# Main.net
KiCad netlist of a schematic drawn in Altium Designer
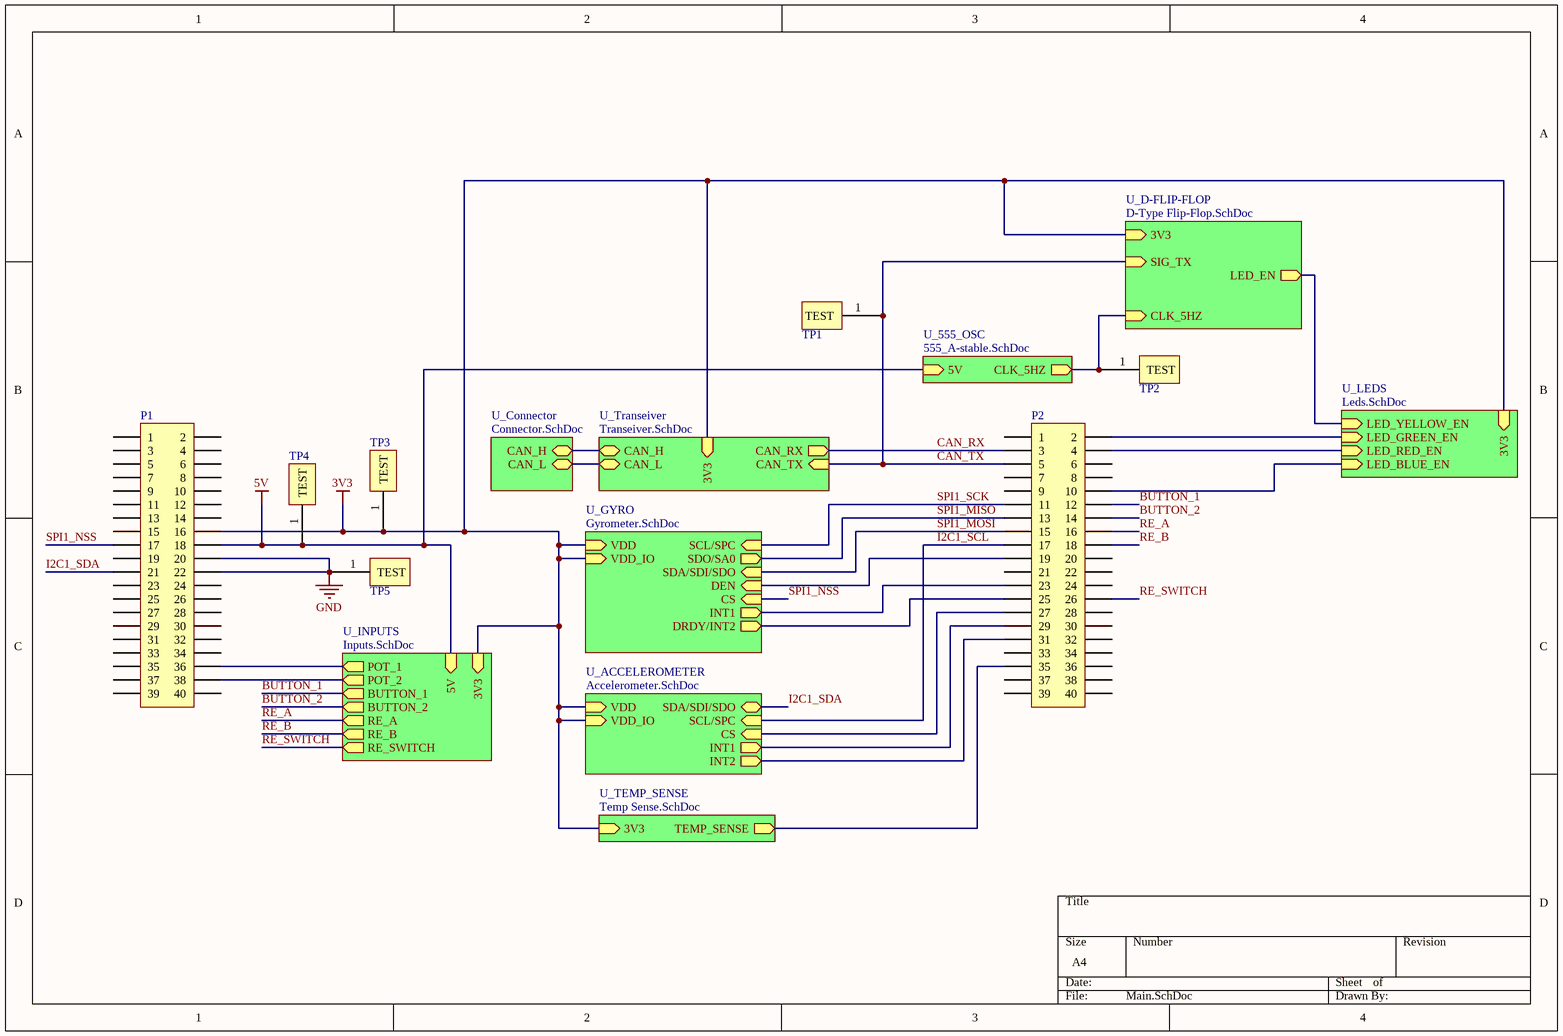
[diagram p0: Main.SchDoc]

(export (version "E")
  (design (tool "Eeschema 10.0.6"))
  (components
    (comp (ref "P1")
      (value "Female Header 20x2_BOTTOM")
      (footprint "FEMALE HDR2X20_BOTTOM")
      (description "CONN HEADR FMALE 20POS .1\" DL AU")
      (libsource (lib "Connectors and Headers") (part "Female Header 20x2_BOTTOM"))
    )
    (comp (ref "P2")
      (value "Female Header 20x2_BOTTOM")
      (footprint "FEMALE HDR2X20_BOTTOM")
      (description "CONN HEADR FMALE 20POS .1\" DL AU")
      (libsource (lib "Connectors and Headers") (part "Female Header 20x2_BOTTOM"))
    )
    (comp (ref "TP1")
      (value "Keystone Electronics 5000")
      (footprint "TEST POINT 5000K")
      (description "TEST POINT PC MINI .040\"D RED")
      (libsource (lib "") (part "Keystone Electronics 5000_2"))
    )
    (comp (ref "TP2")
      (value "Keystone Electronics 5000")
      (footprint "TEST POINT 5000K")
      (description "TEST POINT PC MINI .040\"D RED")
      (libsource (lib "") (part "Keystone Electronics 5000_1"))
    )
    (comp (ref "TP3")
      (value "Keystone Electronics 5000")
      (footprint "TEST POINT 5000K")
      (description "TEST POINT PC MINI .040\"D RED")
      (libsource (lib "Mechanical_Devices") (part "Keystone Electronics 5000"))
    )
    (comp (ref "TP4")
      (value "Keystone Electronics 5000")
      (footprint "TEST POINT 5000K")
      (description "TEST POINT PC MINI .040\"D RED")
      (libsource (lib "Mechanical_Devices") (part "Keystone Electronics 5000"))
    )
    (comp (ref "TP5")
      (value "Keystone Electronics 5000")
      (footprint "TEST POINT 5000K")
      (description "TEST POINT PC MINI .040\"D RED")
      (libsource (lib "") (part "Keystone Electronics 5000_1"))
    )
  )
  (nets
    (net (code "1") (name "/BUTTON_1") (class "Default")
      (node (ref "P2") (pin "12") (pinfunction "12_12") (pintype "passive"))
    )
    (net (code "2") (name "/BUTTON_2") (class "Default")
      (node (ref "P2") (pin "14") (pinfunction "14_14") (pintype "passive"))
    )
    (net (code "5") (name "/CAN_RX") (class "Default")
      (node (ref "P2") (pin "3") (pinfunction "3_3") (pintype "passive"))
    )
    (net (code "6") (name "/CAN_TX") (class "Default")
      (node (ref "P2") (pin "5") (pinfunction "5_5") (pintype "passive"))
      (node (ref "TP1") (pin "1") (pinfunction "TEST_1") (pintype "passive"))
    )
    (net (code "7") (name "/CLK_5HZ") (class "Default")
      (node (ref "TP2") (pin "1") (pinfunction "TEST_1") (pintype "passive"))
    )
    (net (code "8") (name "/CS") (class "Default")
      (node (ref "P2") (pin "27") (pinfunction "27_27") (pintype "passive"))
    )
    (net (code "9") (name "/DEN") (class "Default")
      (node (ref "P2") (pin "19") (pinfunction "19_19") (pintype "passive"))
    )
    (net (code "10") (name "/DRDY{slash}INT2") (class "Default")
      (node (ref "P2") (pin "25") (pinfunction "25_25") (pintype "passive"))
    )
    (net (code "11") (name "/I2C1_SCL") (class "Default")
      (node (ref "P2") (pin "17") (pinfunction "17_17") (pintype "passive"))
    )
    (net (code "12") (name "/I2C1_SDA") (class "Default")
      (node (ref "P1") (pin "21") (pinfunction "21_21") (pintype "passive"))
    )
    (net (code "13") (name "/INT1") (class "Default")
      (node (ref "P2") (pin "29") (pinfunction "29_29") (pintype "passive"))
    )
    (net (code "14") (name "/INT1_1") (class "Default")
      (node (ref "P2") (pin "23") (pinfunction "23_23") (pintype "passive"))
    )
    (net (code "15") (name "/INT2") (class "Default")
      (node (ref "P2") (pin "31") (pinfunction "31_31") (pintype "passive"))
    )
    (net (code "16") (name "/LED_BLUE_EN") (class "Default")
      (node (ref "P2") (pin "10") (pinfunction "10_10") (pintype "passive"))
    )
    (net (code "18") (name "/LED_GREEN_EN") (class "Default")
      (node (ref "P2") (pin "2") (pinfunction "2_2") (pintype "passive"))
    )
    (net (code "19") (name "/LED_RED_EN") (class "Default")
      (node (ref "P2") (pin "4") (pinfunction "4_4") (pintype "passive"))
    )
    (net (code "20") (name "/POT_1") (class "Default")
      (node (ref "P1") (pin "36") (pinfunction "36_36") (pintype "passive"))
    )
    (net (code "21") (name "/POT_2") (class "Default")
      (node (ref "P1") (pin "38") (pinfunction "38_38") (pintype "passive"))
    )
    (net (code "22") (name "/RE_A") (class "Default")
      (node (ref "P2") (pin "16") (pinfunction "16_16") (pintype "passive"))
    )
    (net (code "23") (name "/RE_B") (class "Default")
      (node (ref "P2") (pin "18") (pinfunction "18_18") (pintype "passive"))
    )
    (net (code "24") (name "/RE_SWITCH") (class "Default")
      (node (ref "P2") (pin "26") (pinfunction "26_26") (pintype "passive"))
    )
    (net (code "25") (name "/SPI1_MISO") (class "Default")
      (node (ref "P2") (pin "13") (pinfunction "13_13") (pintype "passive"))
    )
    (net (code "26") (name "/SPI1_MOSI") (class "Default")
      (node (ref "P2") (pin "15") (pinfunction "15_15") (pintype "passive"))
    )
    (net (code "27") (name "/SPI1_NSS") (class "Default")
      (node (ref "P1") (pin "17") (pinfunction "17_17") (pintype "passive"))
    )
    (net (code "28") (name "/SPI1_SCK") (class "Default")
      (node (ref "P2") (pin "11") (pinfunction "11_11") (pintype "passive"))
    )
    (net (code "29") (name "/TEMP_SENSE") (class "Default")
      (node (ref "P2") (pin "35") (pinfunction "35_35") (pintype "passive"))
    )
    (net (code "30") (name "3V3") (class "Default")
      (node (ref "P1") (pin "16") (pinfunction "16_16") (pintype "passive"))
      (node (ref "TP3") (pin "1") (pinfunction "TEST_1") (pintype "passive"))
    )
    (net (code "31") (name "5V") (class "Default")
      (node (ref "P1") (pin "18") (pinfunction "18_18") (pintype "passive"))
      (node (ref "TP4") (pin "1") (pinfunction "TEST_1") (pintype "passive"))
    )
    (net (code "32") (name "GND") (class "Default")
      (node (ref "P1") (pin "20") (pinfunction "20_20") (pintype "passive"))
      (node (ref "P1") (pin "22") (pinfunction "22_22") (pintype "passive"))
      (node (ref "TP5") (pin "1") (pinfunction "TEST_1") (pintype "passive"))
    )
    (net (code "33") (name "unconnected-(P1-Pad1)") (class "Default")
      (node (ref "P1") (pin "1") (pinfunction "1_1") (pintype "passive"))
    )
    (net (code "34") (name "unconnected-(P1-Pad2)") (class "Default")
      (node (ref "P1") (pin "2") (pinfunction "2_2") (pintype "passive"))
    )
    (net (code "35") (name "unconnected-(P1-Pad3)") (class "Default")
      (node (ref "P1") (pin "3") (pinfunction "3_3") (pintype "passive"))
    )
    (net (code "36") (name "unconnected-(P1-Pad4)") (class "Default")
      (node (ref "P1") (pin "4") (pinfunction "4_4") (pintype "passive"))
    )
    (net (code "37") (name "unconnected-(P1-Pad5)") (class "Default")
      (node (ref "P1") (pin "5") (pinfunction "5_5") (pintype "passive"))
    )
    (net (code "38") (name "unconnected-(P1-Pad6)") (class "Default")
      (node (ref "P1") (pin "6") (pinfunction "6_6") (pintype "passive"))
    )
    (net (code "39") (name "unconnected-(P1-Pad7)") (class "Default")
      (node (ref "P1") (pin "7") (pinfunction "7_7") (pintype "passive"))
    )
    (net (code "40") (name "unconnected-(P1-Pad8)") (class "Default")
      (node (ref "P1") (pin "8") (pinfunction "8_8") (pintype "passive"))
    )
    (net (code "41") (name "unconnected-(P1-Pad9)") (class "Default")
      (node (ref "P1") (pin "9") (pinfunction "9_9") (pintype "passive"))
    )
    (net (code "42") (name "unconnected-(P1-Pad10)") (class "Default")
      (node (ref "P1") (pin "10") (pinfunction "10_10") (pintype "passive"))
    )
    (net (code "43") (name "unconnected-(P1-Pad11)") (class "Default")
      (node (ref "P1") (pin "11") (pinfunction "11_11") (pintype "passive"))
    )
    (net (code "44") (name "unconnected-(P1-Pad12)") (class "Default")
      (node (ref "P1") (pin "12") (pinfunction "12_12") (pintype "passive"))
    )
    (net (code "45") (name "unconnected-(P1-Pad13)") (class "Default")
      (node (ref "P1") (pin "13") (pinfunction "13_13") (pintype "passive"))
    )
    (net (code "46") (name "unconnected-(P1-Pad14)") (class "Default")
      (node (ref "P1") (pin "14") (pinfunction "14_14") (pintype "passive"))
    )
    (net (code "47") (name "unconnected-(P1-Pad15)") (class "Default")
      (node (ref "P1") (pin "15") (pinfunction "15_15") (pintype "passive"))
    )
    (net (code "48") (name "unconnected-(P1-Pad19)") (class "Default")
      (node (ref "P1") (pin "19") (pinfunction "19_19") (pintype "passive"))
    )
    (net (code "49") (name "unconnected-(P1-Pad23)") (class "Default")
      (node (ref "P1") (pin "23") (pinfunction "23_23") (pintype "passive"))
    )
    (net (code "50") (name "unconnected-(P1-Pad24)") (class "Default")
      (node (ref "P1") (pin "24") (pinfunction "24_24") (pintype "passive"))
    )
    (net (code "51") (name "unconnected-(P1-Pad25)") (class "Default")
      (node (ref "P1") (pin "25") (pinfunction "25_25") (pintype "passive"))
    )
    (net (code "52") (name "unconnected-(P1-Pad26)") (class "Default")
      (node (ref "P1") (pin "26") (pinfunction "26_26") (pintype "passive"))
    )
    (net (code "53") (name "unconnected-(P1-Pad27)") (class "Default")
      (node (ref "P1") (pin "27") (pinfunction "27_27") (pintype "passive"))
    )
    (net (code "54") (name "unconnected-(P1-Pad28)") (class "Default")
      (node (ref "P1") (pin "28") (pinfunction "28_28") (pintype "passive"))
    )
    (net (code "55") (name "unconnected-(P1-Pad29)") (class "Default")
      (node (ref "P1") (pin "29") (pinfunction "29_29") (pintype "passive"))
    )
    (net (code "56") (name "unconnected-(P1-Pad30)") (class "Default")
      (node (ref "P1") (pin "30") (pinfunction "30_30") (pintype "passive"))
    )
    (net (code "57") (name "unconnected-(P1-Pad31)") (class "Default")
      (node (ref "P1") (pin "31") (pinfunction "31_31") (pintype "passive"))
    )
    (net (code "58") (name "unconnected-(P1-Pad32)") (class "Default")
      (node (ref "P1") (pin "32") (pinfunction "32_32") (pintype "passive"))
    )
    (net (code "59") (name "unconnected-(P1-Pad33)") (class "Default")
      (node (ref "P1") (pin "33") (pinfunction "33_33") (pintype "passive"))
    )
    (net (code "60") (name "unconnected-(P1-Pad34)") (class "Default")
      (node (ref "P1") (pin "34") (pinfunction "34_34") (pintype "passive"))
    )
    (net (code "61") (name "unconnected-(P1-Pad35)") (class "Default")
      (node (ref "P1") (pin "35") (pinfunction "35_35") (pintype "passive"))
    )
    (net (code "62") (name "unconnected-(P1-Pad37)") (class "Default")
      (node (ref "P1") (pin "37") (pinfunction "37_37") (pintype "passive"))
    )
    (net (code "63") (name "unconnected-(P1-Pad39)") (class "Default")
      (node (ref "P1") (pin "39") (pinfunction "39_39") (pintype "passive"))
    )
    (net (code "64") (name "unconnected-(P1-Pad40)") (class "Default")
      (node (ref "P1") (pin "40") (pinfunction "40_40") (pintype "passive"))
    )
    (net (code "65") (name "unconnected-(P2-Pad1)") (class "Default")
      (node (ref "P2") (pin "1") (pinfunction "1_1") (pintype "passive"))
    )
    (net (code "66") (name "unconnected-(P2-Pad6)") (class "Default")
      (node (ref "P2") (pin "6") (pinfunction "6_6") (pintype "passive"))
    )
    (net (code "67") (name "unconnected-(P2-Pad7)") (class "Default")
      (node (ref "P2") (pin "7") (pinfunction "7_7") (pintype "passive"))
    )
    (net (code "68") (name "unconnected-(P2-Pad8)") (class "Default")
      (node (ref "P2") (pin "8") (pinfunction "8_8") (pintype "passive"))
    )
    (net (code "69") (name "unconnected-(P2-Pad9)") (class "Default")
      (node (ref "P2") (pin "9") (pinfunction "9_9") (pintype "passive"))
    )
    (net (code "70") (name "unconnected-(P2-Pad20)") (class "Default")
      (node (ref "P2") (pin "20") (pinfunction "20_20") (pintype "passive"))
    )
    (net (code "71") (name "unconnected-(P2-Pad21)") (class "Default")
      (node (ref "P2") (pin "21") (pinfunction "21_21") (pintype "passive"))
    )
    (net (code "72") (name "unconnected-(P2-Pad22)") (class "Default")
      (node (ref "P2") (pin "22") (pinfunction "22_22") (pintype "passive"))
    )
    (net (code "73") (name "unconnected-(P2-Pad24)") (class "Default")
      (node (ref "P2") (pin "24") (pinfunction "24_24") (pintype "passive"))
    )
    (net (code "74") (name "unconnected-(P2-Pad28)") (class "Default")
      (node (ref "P2") (pin "28") (pinfunction "28_28") (pintype "passive"))
    )
    (net (code "75") (name "unconnected-(P2-Pad30)") (class "Default")
      (node (ref "P2") (pin "30") (pinfunction "30_30") (pintype "passive"))
    )
    (net (code "76") (name "unconnected-(P2-Pad32)") (class "Default")
      (node (ref "P2") (pin "32") (pinfunction "32_32") (pintype "passive"))
    )
    (net (code "77") (name "unconnected-(P2-Pad33)") (class "Default")
      (node (ref "P2") (pin "33") (pinfunction "33_33") (pintype "passive"))
    )
    (net (code "78") (name "unconnected-(P2-Pad34)") (class "Default")
      (node (ref "P2") (pin "34") (pinfunction "34_34") (pintype "passive"))
    )
    (net (code "79") (name "unconnected-(P2-Pad36)") (class "Default")
      (node (ref "P2") (pin "36") (pinfunction "36_36") (pintype "passive"))
    )
    (net (code "80") (name "unconnected-(P2-Pad37)") (class "Default")
      (node (ref "P2") (pin "37") (pinfunction "37_37") (pintype "passive"))
    )
    (net (code "81") (name "unconnected-(P2-Pad38)") (class "Default")
      (node (ref "P2") (pin "38") (pinfunction "38_38") (pintype "passive"))
    )
    (net (code "82") (name "unconnected-(P2-Pad39)") (class "Default")
      (node (ref "P2") (pin "39") (pinfunction "39_39") (pintype "passive"))
    )
    (net (code "83") (name "unconnected-(P2-Pad40)") (class "Default")
      (node (ref "P2") (pin "40") (pinfunction "40_40") (pintype "passive"))
    )
  )
)
